# Projekt2.net
KiCad netlist of a schematic drawn in EAGLE
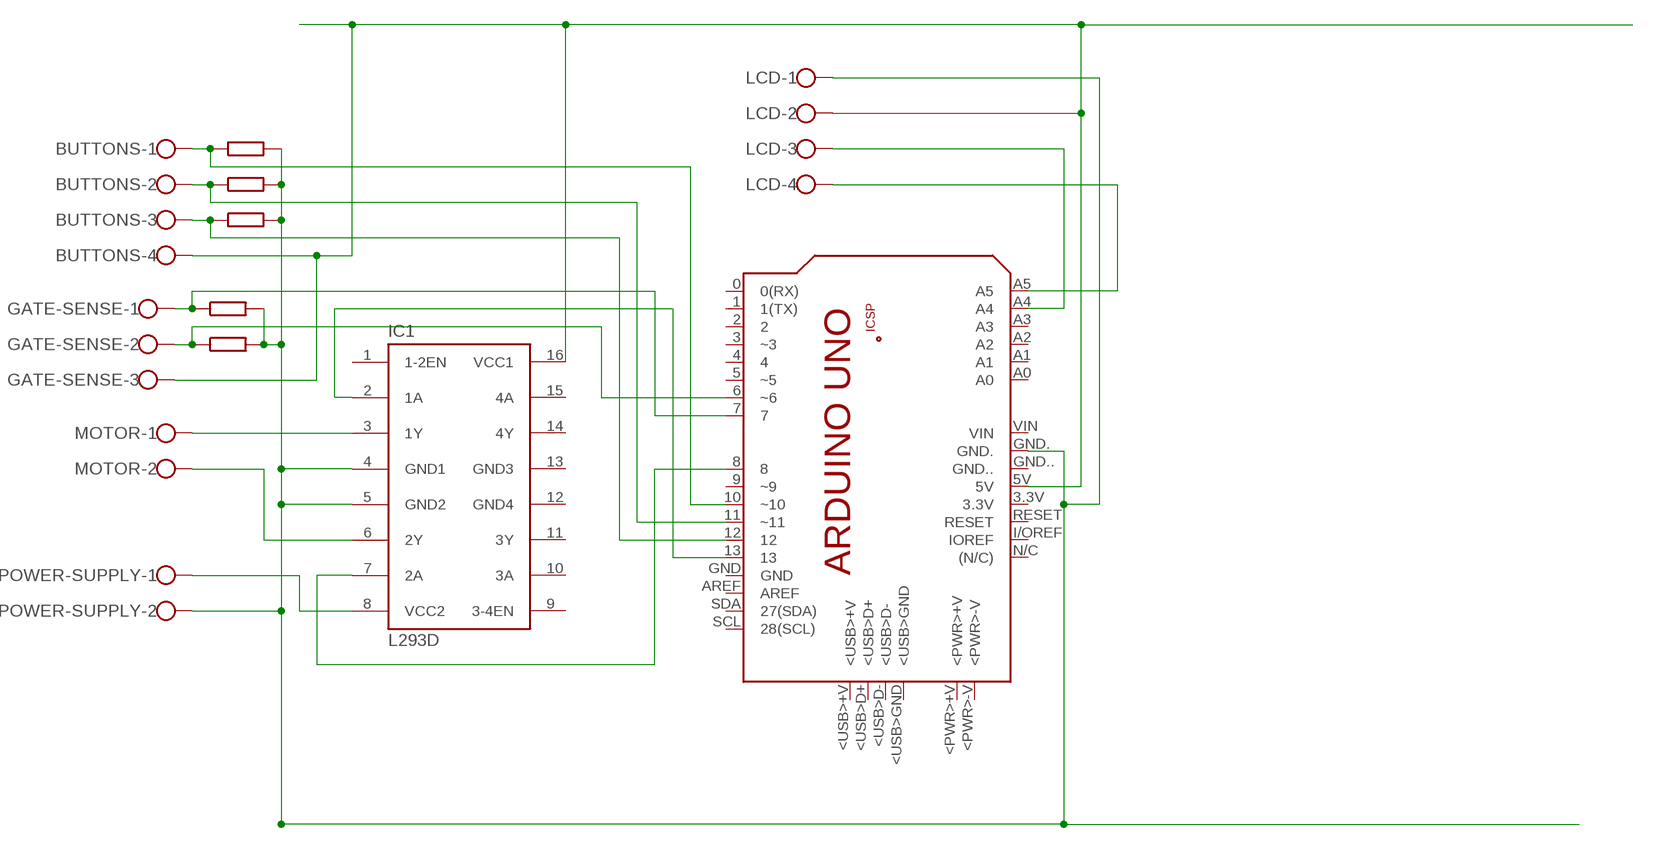
[diagram p0: schematic, sheet 1]

(export (version "E")
  (design (tool "Eeschema 10.0.6"))
  (components
    (comp (ref "BUTTONS")
      (value "W239-104")
      (footprint "eagle-import:W239-104")
      (libsource (lib "eagle-import") (part "W239-104"))
    )
    (comp (ref "GATE-SENSE")
      (value "W237-103")
      (footprint "eagle-import:W237-103")
      (fields (field (name "MPN") "237-103"))
      (libsource (lib "eagle-import") (part "W237-103"))
    )
    (comp (ref "IC1")
      (value "L293D")
      (footprint "eagle-import:DIL16")
      (libsource (lib "eagle-import") (part "L293D"))
    )
    (comp (ref "LCD")
      (value "W237-4")
      (footprint "eagle-import:W237-4")
      (libsource (lib "eagle-import") (part "W237-4"))
    )
    (comp (ref "MOTOR")
      (value "W237-102")
      (footprint "eagle-import:W237-102")
      (fields (field (name "MPN") "237-102"))
      (libsource (lib "eagle-import") (part "W237-102"))
    )
    (comp (ref "PCB1")
      (value "ARDUINO_UNO")
      (footprint "eagle-import:ARDUINO_UNO")
      (libsource (lib "eagle-import") (part "ARDUINO_UNO"))
    )
    (comp (ref "POWER-SUPPLY")
      (value "W237-102")
      (footprint "eagle-import:W237-102")
      (fields (field (name "MPN") "237-102"))
      (libsource (lib "eagle-import") (part "W237-102"))
    )
  )
  (nets
    (net (code "1") (name "/GND3") (class "Default")
      (node (ref "IC1") (pin "13") (pinfunction "GND3_13") (pintype "power_in"))
    )
    (net (code "2") (name "/GND4") (class "Default")
      (node (ref "IC1") (pin "12") (pinfunction "GND4_12") (pintype "power_in"))
    )
    (net (code "3") (name "Net-(BUTTONSA-KL)") (class "Default")
      (node (ref "BUTTONS") (pin "1") (pinfunction "KL_1") (pintype "passive"))
      (node (ref "PCB1") (pin "10") (pinfunction "~{10}_10") (pintype "bidirectional"))
    )
    (net (code "4") (name "Net-(BUTTONSB-KL)") (class "Default")
      (node (ref "BUTTONS") (pin "2") (pinfunction "KL_2") (pintype "passive"))
      (node (ref "PCB1") (pin "11") (pinfunction "~{11}_11") (pintype "bidirectional"))
    )
    (net (code "5") (name "Net-(BUTTONSC-KL)") (class "Default")
      (node (ref "BUTTONS") (pin "3") (pinfunction "KL_3") (pintype "passive"))
      (node (ref "PCB1") (pin "12") (pinfunction "12_12") (pintype "bidirectional"))
    )
    (net (code "6") (name "Net-(BUTTONSD-KL)") (class "Default")
      (node (ref "BUTTONS") (pin "4") (pinfunction "KL_4") (pintype "passive"))
      (node (ref "GATE-SENSE") (pin "3") (pinfunction "KL_3") (pintype "passive"))
      (node (ref "IC1") (pin "16") (pinfunction "VCC1_16") (pintype "power_in"))
      (node (ref "LCD") (pin "2") (pinfunction "KL_2") (pintype "passive"))
      (node (ref "PCB1") (pin "5V") (pinfunction "5V_5V") (pintype "bidirectional"))
    )
    (net (code "7") (name "Net-(GATE-SENSEA-KL)") (class "Default")
      (node (ref "GATE-SENSE") (pin "1") (pinfunction "KL_1") (pintype "passive"))
      (node (ref "PCB1") (pin "7") (pinfunction "7_7") (pintype "bidirectional"))
    )
    (net (code "8") (name "Net-(GATE-SENSEB-KL)") (class "Default")
      (node (ref "GATE-SENSE") (pin "2") (pinfunction "KL_2") (pintype "passive"))
      (node (ref "PCB1") (pin "6") (pinfunction "~{6}_6") (pintype "bidirectional"))
    )
    (net (code "9") (name "Net-(IC1-1A)") (class "Default")
      (node (ref "IC1") (pin "2") (pinfunction "1A_2") (pintype "input"))
      (node (ref "PCB1") (pin "13") (pinfunction "13_13") (pintype "bidirectional"))
    )
    (net (code "10") (name "Net-(IC1-1Y)") (class "Default")
      (node (ref "IC1") (pin "3") (pinfunction "1Y_3") (pintype "output"))
      (node (ref "MOTOR") (pin "1") (pinfunction "KL_1") (pintype "passive"))
    )
    (net (code "11") (name "Net-(IC1-2A)") (class "Default")
      (node (ref "IC1") (pin "7") (pinfunction "2A_7") (pintype "input"))
      (node (ref "PCB1") (pin "8") (pinfunction "8_8") (pintype "bidirectional"))
    )
    (net (code "12") (name "Net-(IC1-2Y)") (class "Default")
      (node (ref "IC1") (pin "6") (pinfunction "2Y_6") (pintype "output"))
      (node (ref "MOTOR") (pin "2") (pinfunction "KL_2") (pintype "passive"))
    )
    (net (code "13") (name "Net-(IC1-GND1)") (class "Default")
      (node (ref "IC1") (pin "4") (pinfunction "GND1_4") (pintype "power_in"))
      (node (ref "IC1") (pin "5") (pinfunction "GND2_5") (pintype "power_in"))
      (node (ref "LCD") (pin "1") (pinfunction "KL_1") (pintype "passive"))
      (node (ref "PCB1") (pin "GND.") (pinfunction "GND._GND.") (pintype "bidirectional"))
      (node (ref "POWER-SUPPLY") (pin "2") (pinfunction "KL_2") (pintype "passive"))
    )
    (net (code "14") (name "Net-(IC1-VCC2)") (class "Default")
      (node (ref "IC1") (pin "8") (pinfunction "VCC2_8") (pintype "power_in"))
      (node (ref "POWER-SUPPLY") (pin "1") (pinfunction "KL_1") (pintype "passive"))
    )
    (net (code "15") (name "Net-(LCDC-KL)") (class "Default")
      (node (ref "LCD") (pin "3") (pinfunction "KL_3") (pintype "passive"))
      (node (ref "PCB1") (pin "A4") (pinfunction "A4_A4") (pintype "bidirectional"))
    )
    (net (code "16") (name "Net-(LCDD-KL)") (class "Default")
      (node (ref "LCD") (pin "4") (pinfunction "KL_4") (pintype "passive"))
      (node (ref "PCB1") (pin "A5") (pinfunction "A5_A5") (pintype "bidirectional"))
    )
    (net (code "17") (name "unconnected-(IC1-1-2EN-Pad1)") (class "Default")
      (node (ref "IC1") (pin "1") (pinfunction "1-2EN_1") (pintype "input"))
    )
    (net (code "18") (name "unconnected-(IC1-3-4EN-Pad9)") (class "Default")
      (node (ref "IC1") (pin "9") (pinfunction "3-4EN_9") (pintype "input"))
    )
    (net (code "19") (name "unconnected-(IC1-3A-Pad10)") (class "Default")
      (node (ref "IC1") (pin "10") (pinfunction "3A_10") (pintype "input"))
    )
    (net (code "20") (name "unconnected-(IC1-3Y-Pad11)") (class "Default")
      (node (ref "IC1") (pin "11") (pinfunction "3Y_11") (pintype "output"))
    )
    (net (code "21") (name "unconnected-(IC1-4A-Pad15)") (class "Default")
      (node (ref "IC1") (pin "15") (pinfunction "4A_15") (pintype "input"))
    )
    (net (code "22") (name "unconnected-(IC1-4Y-Pad14)") (class "Default")
      (node (ref "IC1") (pin "14") (pinfunction "4Y_14") (pintype "output"))
    )
    (net (code "23") (name "unconnected-(PCB1-(N{slash}C)-PadN{slash}C)") (class "Default")
      (node (ref "PCB1") (pin "N/C") (pinfunction "(N/C)_N/C") (pintype "bidirectional"))
    )
    (net (code "24") (name "unconnected-(PCB1-0(RX)-Pad0)") (class "Default")
      (node (ref "PCB1") (pin "0") (pinfunction "0(RX)_0") (pintype "bidirectional"))
    )
    (net (code "25") (name "unconnected-(PCB1-1(TX)-Pad1)") (class "Default")
      (node (ref "PCB1") (pin "1") (pinfunction "1(TX)_1") (pintype "bidirectional"))
    )
    (net (code "26") (name "unconnected-(PCB1-27(SDA)-PadSDA)") (class "Default")
      (node (ref "PCB1") (pin "SDA") (pinfunction "27(SDA)_SDA") (pintype "bidirectional"))
    )
    (net (code "27") (name "unconnected-(PCB1-28(SCL)-PadSCL)") (class "Default")
      (node (ref "PCB1") (pin "SCL") (pinfunction "28(SCL)_SCL") (pintype "bidirectional"))
    )
    (net (code "28") (name "unconnected-(PCB1-IOREF-PadI{slash}OREF)") (class "Default")
      (node (ref "PCB1") (pin "I/OREF") (pinfunction "IOREF_I/OREF") (pintype "bidirectional"))
    )
    (net (code "29") (name "unconnected-(PCB1-Pad+5V)") (class "Default")
      (node (ref "PCB1") (pin "+5V") (pinfunction "+5V_+5V") (pintype "bidirectional"))
    )
    (net (code "30") (name "unconnected-(PCB1-Pad2)") (class "Default")
      (node (ref "PCB1") (pin "2") (pinfunction "2_2") (pintype "bidirectional"))
    )
    (net (code "31") (name "unconnected-(PCB1-Pad3.3V)") (class "Default")
      (node (ref "PCB1") (pin "3.3V") (pinfunction "3.3V_3.3V") (pintype "bidirectional"))
    )
    (net (code "32") (name "unconnected-(PCB1-Pad4)") (class "Default")
      (node (ref "PCB1") (pin "4") (pinfunction "4_4") (pintype "bidirectional"))
    )
    (net (code "33") (name "unconnected-(PCB1-Pad<PWR>+V)") (class "Default")
      (node (ref "PCB1") (pin "<PWR>+V") (pinfunction "<PWR>+V_<PWR>+V") (pintype "bidirectional"))
    )
    (net (code "34") (name "unconnected-(PCB1-Pad<PWR>-V)") (class "Default")
      (node (ref "PCB1") (pin "<PWR>-V") (pinfunction "<PWR>-V_<PWR>-V") (pintype "bidirectional"))
    )
    (net (code "35") (name "unconnected-(PCB1-Pad<USB>+V)") (class "Default")
      (node (ref "PCB1") (pin "<USB>+V") (pinfunction "<USB>+V_<USB>+V") (pintype "bidirectional"))
    )
    (net (code "36") (name "unconnected-(PCB1-Pad<USB>D+)") (class "Default")
      (node (ref "PCB1") (pin "<USB>D+") (pinfunction "<USB>D+_<USB>D+") (pintype "bidirectional"))
    )
    (net (code "37") (name "unconnected-(PCB1-Pad<USB>D-)") (class "Default")
      (node (ref "PCB1") (pin "<USB>D-") (pinfunction "<USB>D-_<USB>D-") (pintype "bidirectional"))
    )
    (net (code "38") (name "unconnected-(PCB1-Pad<USB>GND)") (class "Default")
      (node (ref "PCB1") (pin "<USB>GND") (pinfunction "<USB>GND_<USB>GND") (pintype "bidirectional"))
    )
    (net (code "39") (name "unconnected-(PCB1-PadA0)") (class "Default")
      (node (ref "PCB1") (pin "A0") (pinfunction "A0_A0") (pintype "bidirectional"))
    )
    (net (code "40") (name "unconnected-(PCB1-PadA1)") (class "Default")
      (node (ref "PCB1") (pin "A1") (pinfunction "A1_A1") (pintype "bidirectional"))
    )
    (net (code "41") (name "unconnected-(PCB1-PadA2)") (class "Default")
      (node (ref "PCB1") (pin "A2") (pinfunction "A2_A2") (pintype "bidirectional"))
    )
    (net (code "42") (name "unconnected-(PCB1-PadA3)") (class "Default")
      (node (ref "PCB1") (pin "A3") (pinfunction "A3_A3") (pintype "bidirectional"))
    )
    (net (code "43") (name "unconnected-(PCB1-PadAREF)") (class "Default")
      (node (ref "PCB1") (pin "AREF") (pinfunction "AREF_AREF") (pintype "bidirectional"))
    )
    (net (code "44") (name "unconnected-(PCB1-PadGND)") (class "Default")
      (node (ref "PCB1") (pin "GND") (pinfunction "GND_GND") (pintype "bidirectional"))
    )
    (net (code "45") (name "unconnected-(PCB1-PadGND..)") (class "Default")
      (node (ref "PCB1") (pin "GND..") (pinfunction "GND.._GND..") (pintype "bidirectional"))
    )
    (net (code "46") (name "unconnected-(PCB1-PadGND_)") (class "Default")
      (node (ref "PCB1") (pin "GND_") (pinfunction "GND__GND_") (pintype "bidirectional"))
    )
    (net (code "47") (name "unconnected-(PCB1-PadMISO)") (class "Default")
      (node (ref "PCB1") (pin "MISO") (pinfunction "MISO_MISO") (pintype "bidirectional"))
    )
    (net (code "48") (name "unconnected-(PCB1-PadMOSI)") (class "Default")
      (node (ref "PCB1") (pin "MOSI") (pinfunction "MOSI_MOSI") (pintype "bidirectional"))
    )
    (net (code "49") (name "unconnected-(PCB1-PadRESET)") (class "Default")
      (node (ref "PCB1") (pin "RESET") (pinfunction "RESET_RESET") (pintype "bidirectional"))
    )
    (net (code "50") (name "unconnected-(PCB1-PadRESET.)") (class "Default")
      (node (ref "PCB1") (pin "RESET.") (pinfunction "RESET._RESET.") (pintype "bidirectional"))
    )
    (net (code "51") (name "unconnected-(PCB1-PadSCK)") (class "Default")
      (node (ref "PCB1") (pin "SCK") (pinfunction "SCK_SCK") (pintype "bidirectional"))
    )
    (net (code "52") (name "unconnected-(PCB1-PadVIN)") (class "Default")
      (node (ref "PCB1") (pin "VIN") (pinfunction "VIN_VIN") (pintype "bidirectional"))
    )
    (net (code "53") (name "unconnected-(PCB1-~{3}-Pad3)") (class "Default")
      (node (ref "PCB1") (pin "3") (pinfunction "~{3}_3") (pintype "bidirectional"))
    )
    (net (code "54") (name "unconnected-(PCB1-~{5}-Pad5)") (class "Default")
      (node (ref "PCB1") (pin "5") (pinfunction "~{5}_5") (pintype "bidirectional"))
    )
    (net (code "55") (name "unconnected-(PCB1-~{9}-Pad9)") (class "Default")
      (node (ref "PCB1") (pin "9") (pinfunction "~{9}_9") (pintype "bidirectional"))
    )
  )
)
